# PSU_MAX1831_1V2_ALT.net
KiCad netlist of a schematic drawn in Altium Designer
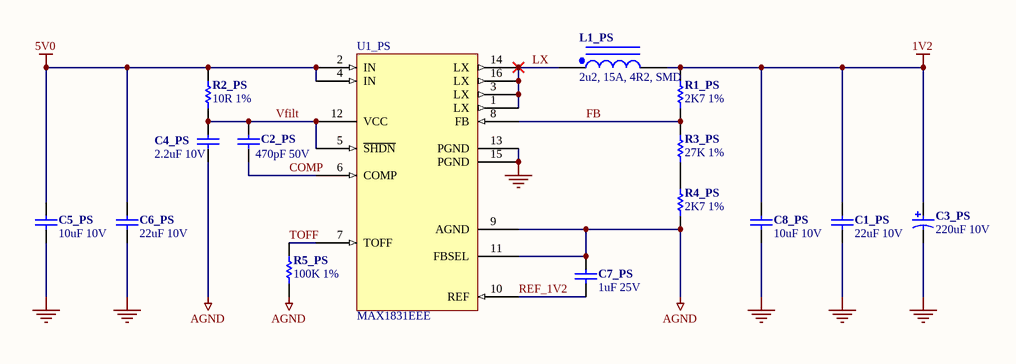
[diagram p0: PSU_MAX1831_1V2_ALT.SchDoc]

(export (version "E")
  (design (tool "Eeschema 10.0.6"))
  (components
    (comp (ref "C1_PS")
      (value "22uF 10V")
      (footprint "CAPC3225-STAR")
      (description "Capacitor, Ceramic, 22uF -20%/+80% 10V 1210 (3225) Y5V")
      (fields (field (name "TOLERANCE") "-20 / +80 %"))
      (libsource (lib "AltiumDesignLibrary") (part "CAP-NP"))
    )
    (comp (ref "C2_PS")
      (value "470pF 50V")
      (footprint "CAPC1005-STAR")
      (description "Capacitor, Ceramic, 470pF 5% 50V 0402 (1005) COG")
      (fields (field (name "TOLERANCE") "5 %"))
      (libsource (lib "AltiumDesignLibrary") (part "CAP-NP"))
    )
    (comp (ref "C3_PS")
      (value "220uF 10V")
      (footprint "CAPC7343-STAR")
      (description "Capacitor, Tantalum, 220uF 10% 10V MCCT-D (7343-31)")
      (fields (field (name "TOLERANCE") "10 %"))
      (libsource (lib "AltiumDesignLibrary") (part "CAP-P"))
    )
    (comp (ref "C4_PS")
      (value "2.2uF 10V")
      (footprint "CAPC1608-STAR")
      (description "Capacitor, Ceramic, 2.2uF 10% 10V 0603 (1608) X5R")
      (fields (field (name "TOLERANCE") "10 %"))
      (libsource (lib "AltiumDesignLibrary") (part "CAP-NP"))
    )
    (comp (ref "C5_PS")
      (value "10uF 10V")
      (footprint "CAPC2012-STAR")
      (description "Capacitor, Ceramic, 10uF 10% 10V 0805 (2012) X5R")
      (fields (field (name "TOLERANCE") "10 %"))
      (libsource (lib "AltiumDesignLibrary") (part "CAP-NP"))
    )
    (comp (ref "C6_PS")
      (value "22uF 10V")
      (footprint "CAPC3225-STAR")
      (description "Capacitor, Ceramic, 22uF -20%/+80% 10V 1210 (3225) Y5V")
      (fields (field (name "TOLERANCE") "-20 / +80 %"))
      (libsource (lib "AltiumDesignLibrary") (part "CAP-NP"))
    )
    (comp (ref "C7_PS")
      (value "1uF 25V")
      (footprint "CAPC3216-STAR")
      (description "Capacitor, Ceramic, 1uF 10% 25V 1206 (3216) X7R")
      (fields (field (name "TOLERANCE") "10 %"))
      (libsource (lib "AltiumDesignLibrary") (part "CAP-NP"))
    )
    (comp (ref "C8_PS")
      (value "10uF 10V")
      (footprint "CAPC2012-STAR")
      (description "Capacitor, Ceramic, 10uF 10% 10V 0805 (2012) X5R")
      (fields (field (name "TOLERANCE") "10 %"))
      (libsource (lib "AltiumDesignLibrary") (part "CAP-NP"))
    )
    (comp (ref "L1_PS")
      (value "2u2, 15A, 4R2, SMD")
      (footprint "IND-EPCOS-SMD-B82559")
      (description "Inductor, 2.2uH, 15A, 4R2, SMD")
      (libsource (lib "AltiumDesignLibrary") (part "IND-IRON-DOT"))
    )
    (comp (ref "R1_PS")
      (value "2K7 1%")
      (footprint "RESC1005-STAR")
      (description "Resistor, 2K7 1% 0402 (1005)")
      (fields (field (name "TOLERANCE") "1 %"))
      (libsource (lib "AltiumDesignLibrary") (part "RES"))
    )
    (comp (ref "R2_PS")
      (value "10R 1%")
      (footprint "RESC1005-STAR")
      (description "Resistor, 10R 1% 0402 (1005)")
      (fields (field (name "TOLERANCE") "1 %"))
      (libsource (lib "AltiumDesignLibrary") (part "RES"))
    )
    (comp (ref "R3_PS")
      (value "27K 1%")
      (footprint "RESC1005-STAR")
      (description "Resistor, 27K 1% 0402 (1005)")
      (fields (field (name "TOLERANCE") "1 %"))
      (libsource (lib "AltiumDesignLibrary") (part "RES"))
    )
    (comp (ref "R4_PS")
      (value "2K7 1%")
      (footprint "RESC1005-STAR")
      (description "Resistor, 2K7 1% 0402 (1005)")
      (fields (field (name "TOLERANCE") "1 %"))
      (libsource (lib "AltiumDesignLibrary") (part "RES"))
    )
    (comp (ref "R5_PS")
      (value "100K 1%")
      (footprint "RESC1005-STAR")
      (description "Resistor, 100K 1% 0402 (1005)")
      (fields (field (name "TOLERANCE") "1 %"))
      (libsource (lib "AltiumDesignLibrary") (part "RES"))
    )
    (comp (ref "U1_PS")
      (value "MAX1831EEE")
      (footprint "SOP63P602-16")
      (libsource (lib "AltiumDesignLibrary") (part "MAX1831-ALT"))
    )
  )
  (nets
    (net (code "1") (name "/COMP") (class "Default")
      (node (ref "C2_PS") (pin "2") (pinfunction "2_2") (pintype "passive"))
      (node (ref "U1_PS") (pin "6") (pinfunction "COMP_6") (pintype "input"))
    )
    (net (code "2") (name "/FB") (class "Default")
      (node (ref "R1_PS") (pin "2") (pinfunction "2_2") (pintype "passive"))
      (node (ref "R3_PS") (pin "1") (pinfunction "1_1") (pintype "passive"))
      (node (ref "U1_PS") (pin "8") (pinfunction "FB_8") (pintype "input"))
    )
    (net (code "3") (name "/LX") (class "Default")
      (node (ref "L1_PS") (pin "1") (pinfunction "1_1") (pintype "passive"))
      (node (ref "U1_PS") (pin "1") (pinfunction "LX_1") (pintype "output"))
      (node (ref "U1_PS") (pin "14") (pinfunction "LX_14") (pintype "output"))
      (node (ref "U1_PS") (pin "16") (pinfunction "LX_16") (pintype "output"))
      (node (ref "U1_PS") (pin "3") (pinfunction "LX_3") (pintype "output"))
    )
    (net (code "4") (name "/REF_1V2") (class "Default")
      (node (ref "C7_PS") (pin "2") (pinfunction "2_2") (pintype "passive"))
      (node (ref "U1_PS") (pin "10") (pinfunction "REF_10") (pintype "input"))
    )
    (net (code "5") (name "/TOFF") (class "Default")
      (node (ref "R5_PS") (pin "1") (pinfunction "1_1") (pintype "passive"))
      (node (ref "U1_PS") (pin "7") (pinfunction "TOFF_7") (pintype "input"))
    )
    (net (code "6") (name "/Vfilt") (class "Default")
      (node (ref "C2_PS") (pin "1") (pinfunction "1_1") (pintype "passive"))
      (node (ref "C4_PS") (pin "1") (pinfunction "1_1") (pintype "passive"))
      (node (ref "R2_PS") (pin "2") (pinfunction "2_2") (pintype "passive"))
      (node (ref "U1_PS") (pin "12") (pinfunction "VCC_12") (pintype "power_in"))
      (node (ref "U1_PS") (pin "5") (pinfunction "~{SHDN}_5") (pintype "input"))
    )
    (net (code "7") (name "1V2") (class "Default")
      (node (ref "C1_PS") (pin "1") (pinfunction "1_1") (pintype "passive"))
      (node (ref "C3_PS") (pin "1") (pinfunction "1_1") (pintype "passive"))
      (node (ref "C8_PS") (pin "1") (pinfunction "1_1") (pintype "passive"))
      (node (ref "L1_PS") (pin "2") (pinfunction "2_2") (pintype "passive"))
      (node (ref "R1_PS") (pin "1") (pinfunction "1_1") (pintype "passive"))
    )
    (net (code "8") (name "5V0") (class "Default")
      (node (ref "C5_PS") (pin "1") (pinfunction "1_1") (pintype "passive"))
      (node (ref "C6_PS") (pin "1") (pinfunction "1_1") (pintype "passive"))
      (node (ref "R2_PS") (pin "1") (pinfunction "1_1") (pintype "passive"))
      (node (ref "U1_PS") (pin "2") (pinfunction "IN_2") (pintype "input"))
      (node (ref "U1_PS") (pin "4") (pinfunction "IN_4") (pintype "input"))
    )
    (net (code "9") (name "AGND") (class "Default")
      (node (ref "C4_PS") (pin "2") (pinfunction "2_2") (pintype "passive"))
      (node (ref "C7_PS") (pin "1") (pinfunction "1_1") (pintype "passive"))
      (node (ref "R4_PS") (pin "2") (pinfunction "2_2") (pintype "passive"))
      (node (ref "R5_PS") (pin "2") (pinfunction "2_2") (pintype "passive"))
      (node (ref "U1_PS") (pin "11") (pinfunction "FBSEL_11") (pintype "passive"))
      (node (ref "U1_PS") (pin "9") (pinfunction "AGND_9") (pintype "power_in"))
    )
    (net (code "10") (name "GND") (class "Default")
      (node (ref "C1_PS") (pin "2") (pinfunction "2_2") (pintype "passive"))
      (node (ref "C3_PS") (pin "2") (pinfunction "2_2") (pintype "passive"))
      (node (ref "C5_PS") (pin "2") (pinfunction "2_2") (pintype "passive"))
      (node (ref "C6_PS") (pin "2") (pinfunction "2_2") (pintype "passive"))
      (node (ref "C8_PS") (pin "2") (pinfunction "2_2") (pintype "passive"))
      (node (ref "U1_PS") (pin "13") (pinfunction "PGND_13") (pintype "power_in"))
      (node (ref "U1_PS") (pin "15") (pinfunction "PGND_15") (pintype "power_in"))
    )
    (net (code "11") (name "Net-(R3_PS-Pad2)") (class "Default")
      (node (ref "R3_PS") (pin "2") (pinfunction "2_2") (pintype "passive"))
      (node (ref "R4_PS") (pin "1") (pinfunction "1_1") (pintype "passive"))
    )
  )
)
